# Relays.net
KiCad netlist of a schematic drawn in Altium Designer
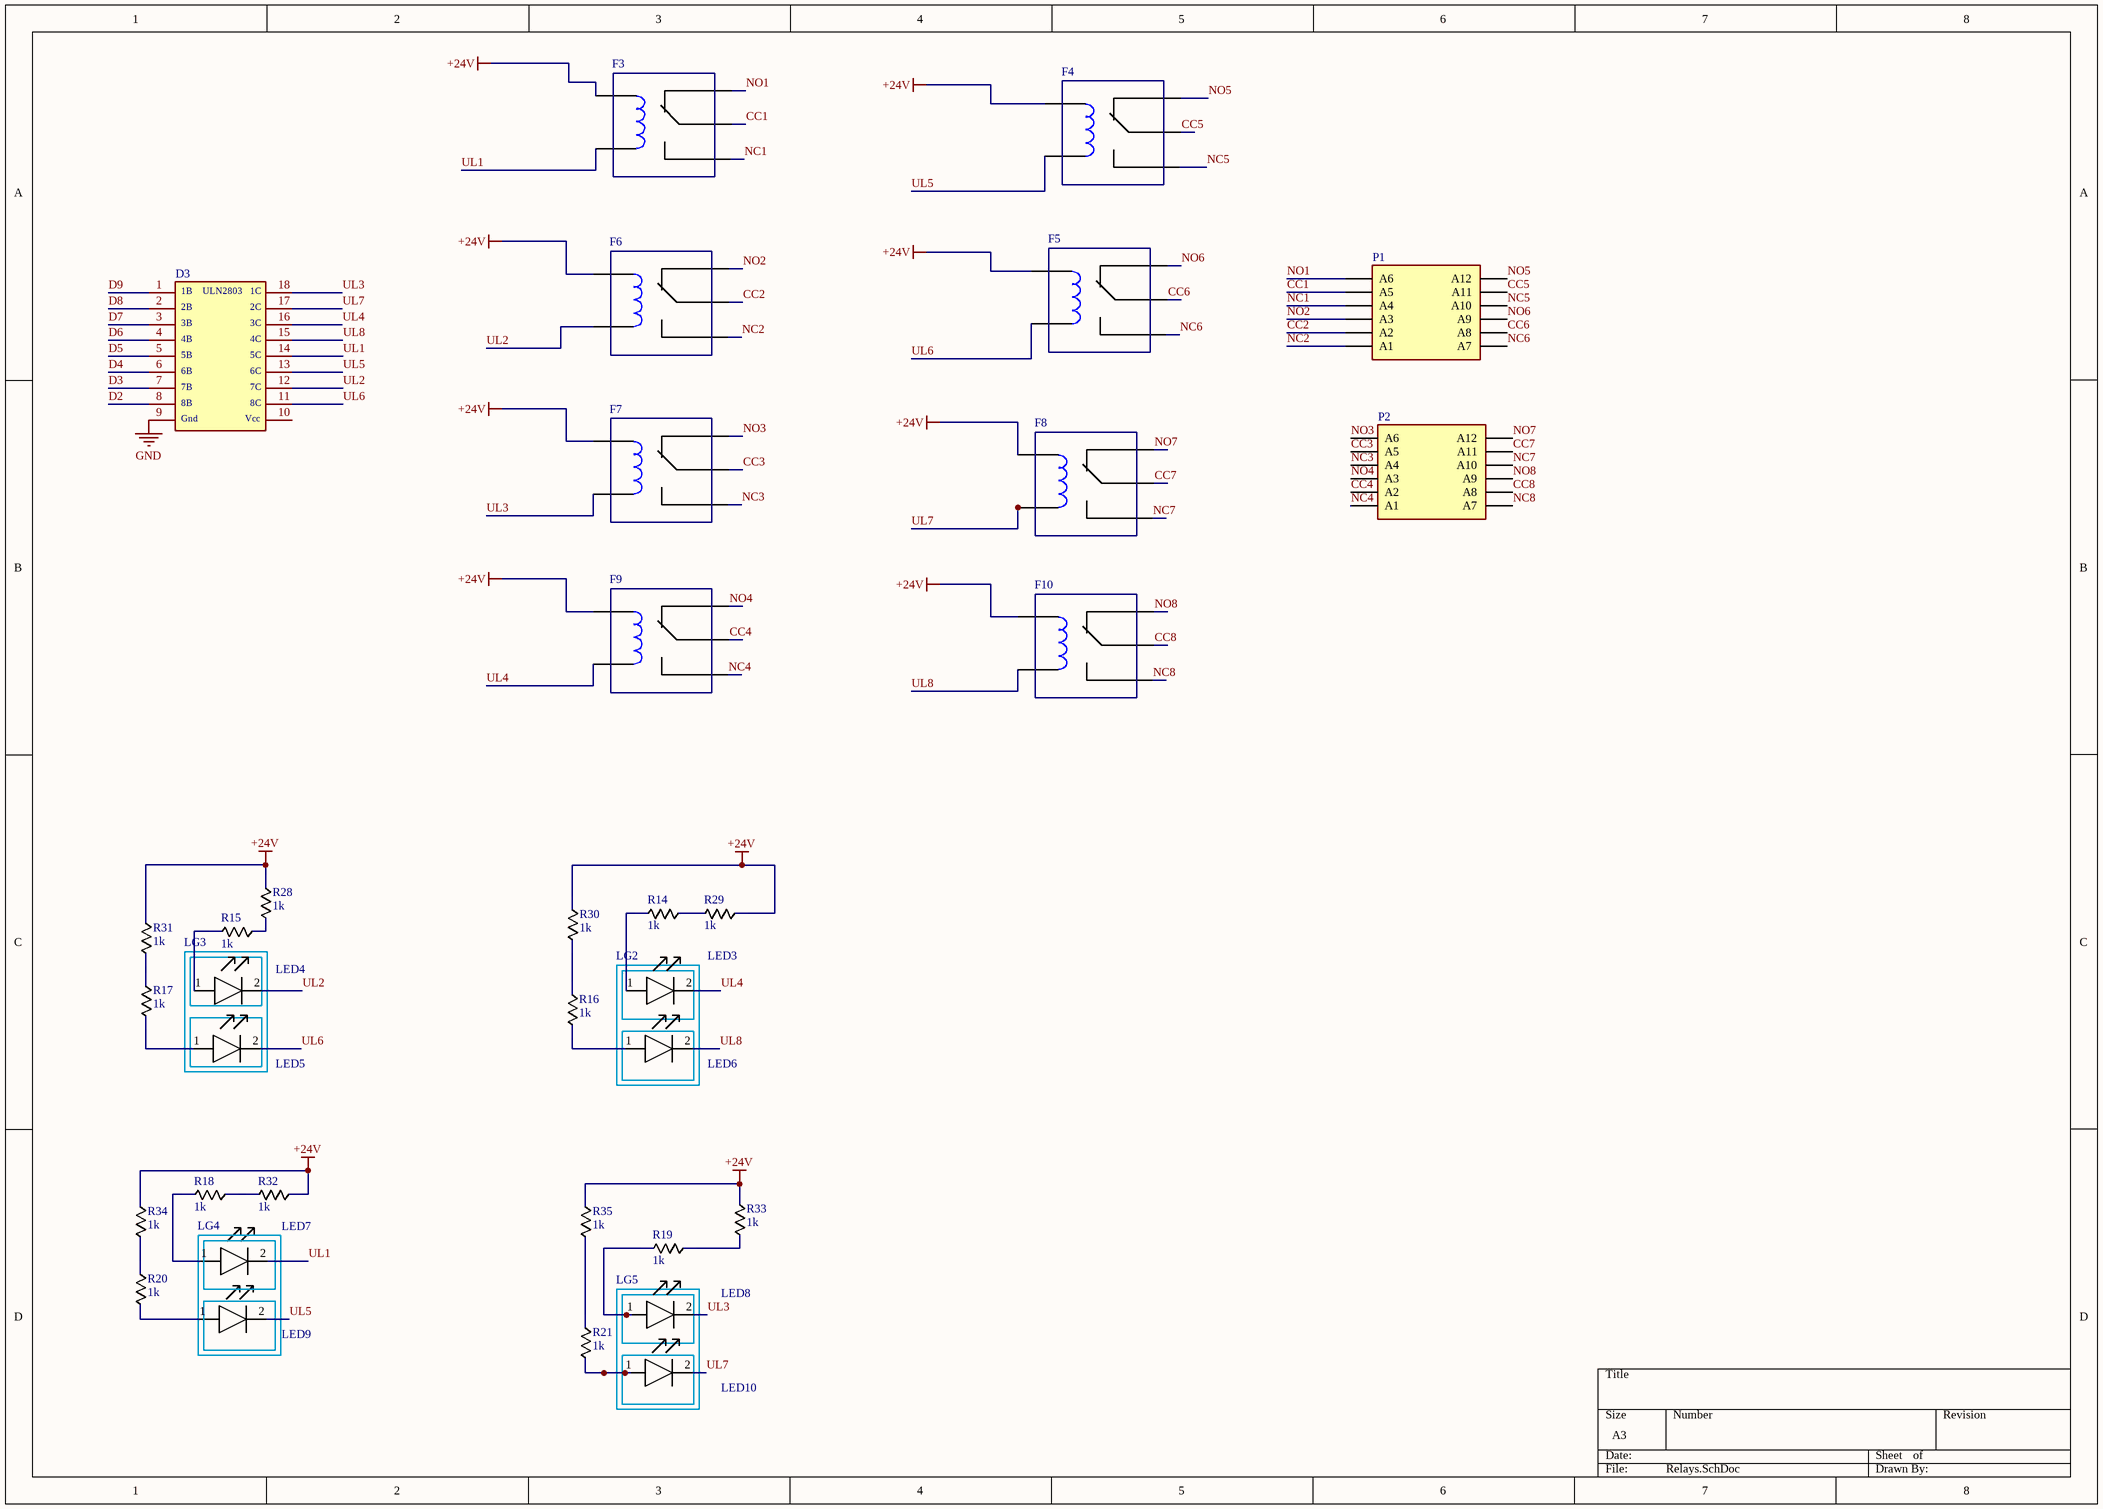
[diagram p0: Relays.SchDoc]

(export (version "E")
  (design (tool "Eeschema 10.0.6"))
  (components
    (comp (ref "D3")
      (value "~")
      (footprint "SOIC 18")
      (fields (field (name "PART NUMBER") "ULN2803ADWR"))
      (libsource (lib "kontr") (part "ULN2803 Darlington_1"))
    )
    (comp (ref "F3")
      (value "~")
      (footprint "413190240010")
      (fields (field (name "PART NUMBER") "G2RL124DC"))
      (libsource (lib "altium-import") (part "root_2__kontr.SCHLIB"))
    )
    (comp (ref "F4")
      (value "~")
      (footprint "413190240010")
      (fields (field (name "PART NUMBER") "G2RL124DC"))
      (libsource (lib "altium-import") (part "root_2__kontr.SCHLIB"))
    )
    (comp (ref "F5")
      (value "~")
      (footprint "413190240010")
      (fields (field (name "PART NUMBER") "G2RL124DC"))
      (libsource (lib "altium-import") (part "root_2__kontr.SCHLIB"))
    )
    (comp (ref "F6")
      (value "~")
      (footprint "413190240010")
      (fields (field (name "PART NUMBER") "G2RL124DC"))
      (libsource (lib "altium-import") (part "root_2__kontr.SCHLIB"))
    )
    (comp (ref "F7")
      (value "~")
      (footprint "413190240010")
      (fields (field (name "PART NUMBER") "G2RL124DC"))
      (libsource (lib "altium-import") (part "root_2__kontr.SCHLIB"))
    )
    (comp (ref "F8")
      (value "~")
      (footprint "413190240010")
      (fields (field (name "PART NUMBER") "G2RL124DC"))
      (libsource (lib "altium-import") (part "root_2__kontr.SCHLIB"))
    )
    (comp (ref "F9")
      (value "~")
      (footprint "413190240010")
      (fields (field (name "PART NUMBER") "G2RL124DC"))
      (libsource (lib "altium-import") (part "root_2__kontr.SCHLIB"))
    )
    (comp (ref "F10")
      (value "~")
      (footprint "413190240010")
      (fields (field (name "PART NUMBER") "G2RL124DC"))
      (libsource (lib "altium-import") (part "root_2__kontr.SCHLIB"))
    )
    (comp (ref "LED3")
      (value "~")
      (footprint "0603 - LED")
      (fields (field (name "PART NUMBER") "KP-1608SGC"))
      (libsource (lib "МЦТР.00010572.00.001") (part "LED 0603"))
    )
    (comp (ref "LED4")
      (value "~")
      (footprint "0603 - LED")
      (fields (field (name "PART NUMBER") "KP-1608SGC"))
      (libsource (lib "МЦТР.00010572.00.001") (part "LED 0603"))
    )
    (comp (ref "LED5")
      (value "~")
      (footprint "0603 - LED")
      (fields (field (name "PART NUMBER") "KP-1608SGC"))
      (libsource (lib "МЦТР.00010572.00.001") (part "LED 0603"))
    )
    (comp (ref "LED6")
      (value "~")
      (footprint "0603 - LED")
      (fields (field (name "PART NUMBER") "KP-1608SGC"))
      (libsource (lib "МЦТР.00010572.00.001") (part "LED 0603"))
    )
    (comp (ref "LED7")
      (value "~")
      (footprint "0603 - LED")
      (fields (field (name "PART NUMBER") "KP-1608SGC"))
      (libsource (lib "МЦТР.00010572.00.001") (part "LED 0603"))
    )
    (comp (ref "LED8")
      (value "~")
      (footprint "0603 - LED")
      (fields (field (name "PART NUMBER") "KP-1608SGC"))
      (libsource (lib "МЦТР.00010572.00.001") (part "LED 0603"))
    )
    (comp (ref "LED9")
      (value "~")
      (footprint "0603 - LED")
      (fields (field (name "PART NUMBER") "KP-1608SGC"))
      (libsource (lib "МЦТР.00010572.00.001") (part "LED 0603"))
    )
    (comp (ref "LED10")
      (value "~")
      (footprint "0603 - LED")
      (fields (field (name "PART NUMBER") "KP-1608SGC"))
      (libsource (lib "МЦТР.00010572.00.001") (part "LED 0603"))
    )
    (comp (ref "LG2")
      (value "~")
      (footprint "LED SMD DayLight")
      (fields (field (name "PART NUMBER") "5151094F"))
      (libsource (lib "МЦТР.00010572.00.001") (part "Light Guide 2"))
    )
    (comp (ref "LG3")
      (value "~")
      (footprint "LED SMD DayLight")
      (fields (field (name "PART NUMBER") "5151094F"))
      (libsource (lib "МЦТР.00010572.00.001") (part "Light Guide 2"))
    )
    (comp (ref "LG4")
      (value "~")
      (footprint "LED SMD DayLight")
      (fields (field (name "PART NUMBER") "5151094F"))
      (libsource (lib "МЦТР.00010572.00.001") (part "Light Guide 2"))
    )
    (comp (ref "LG5")
      (value "~")
      (footprint "LED SMD DayLight")
      (fields (field (name "PART NUMBER") "5151094F"))
      (libsource (lib "МЦТР.00010572.00.001") (part "Light Guide 2"))
    )
    (comp (ref "P1")
      (value "~")
      (footprint "LDO_lib:mcd 1,5/6-G1-3.81")
      (fields (field (name "PART NUMBER") "MCD 1.5/6 Phoenix") (field (name "PUBLISHER") "Altium Limited"))
      (libsource (lib "kontr") (part "MCD 1.5/6 Phoenix"))
    )
    (comp (ref "P2")
      (value "~")
      (footprint "LDO_lib:mcd 1,5/6-G1-3.81")
      (fields (field (name "PART NUMBER") "MCD 1.5/6 Phoenix") (field (name "PUBLISHER") "Altium Limited"))
      (libsource (lib "kontr") (part "MCD 1.5/6 Phoenix"))
    )
    (comp (ref "R14")
      (value "1k")
      (footprint "0603_Res")
      (fields (field (name "PART NUMBER") "RC0603FR-071KL"))
      (libsource (lib "kontr") (part "Resistor 0805"))
    )
    (comp (ref "R15")
      (value "1k")
      (footprint "0603_Res")
      (fields (field (name "PART NUMBER") "RC0603FR-071KL"))
      (libsource (lib "kontr") (part "Resistor 0805"))
    )
    (comp (ref "R16")
      (value "1k")
      (footprint "0603_Res")
      (fields (field (name "PART NUMBER") "RC0603FR-071KL"))
      (libsource (lib "kontr") (part "Resistor 0805"))
    )
    (comp (ref "R17")
      (value "1k")
      (footprint "0603_Res")
      (fields (field (name "PART NUMBER") "RC0603FR-071KL"))
      (libsource (lib "kontr") (part "Resistor 0805"))
    )
    (comp (ref "R18")
      (value "1k")
      (footprint "0603_Res")
      (fields (field (name "PART NUMBER") "RC0603FR-071KL"))
      (libsource (lib "kontr") (part "Resistor 0805"))
    )
    (comp (ref "R19")
      (value "1k")
      (footprint "0603_Res")
      (fields (field (name "PART NUMBER") "RC0603FR-071KL"))
      (libsource (lib "kontr") (part "Resistor 0805"))
    )
    (comp (ref "R20")
      (value "1k")
      (footprint "0603_Res")
      (fields (field (name "PART NUMBER") "RC0603FR-071KL"))
      (libsource (lib "kontr") (part "Resistor 0805"))
    )
    (comp (ref "R21")
      (value "1k")
      (footprint "0603_Res")
      (fields (field (name "PART NUMBER") "RC0603FR-071KL"))
      (libsource (lib "kontr") (part "Resistor 0805"))
    )
    (comp (ref "R28")
      (value "1k")
      (footprint "0603_Res")
      (fields (field (name "PART NUMBER") "RC0603FR-071KL"))
      (libsource (lib "kontr") (part "Resistor 0805"))
    )
    (comp (ref "R29")
      (value "1k")
      (footprint "0603_Res")
      (fields (field (name "PART NUMBER") "RC0603FR-071KL"))
      (libsource (lib "kontr") (part "Resistor 0805"))
    )
    (comp (ref "R30")
      (value "1k")
      (footprint "0603_Res")
      (fields (field (name "PART NUMBER") "RC0603FR-071KL"))
      (libsource (lib "kontr") (part "Resistor 0805"))
    )
    (comp (ref "R31")
      (value "1k")
      (footprint "0603_Res")
      (fields (field (name "PART NUMBER") "RC0603FR-071KL"))
      (libsource (lib "kontr") (part "Resistor 0805"))
    )
    (comp (ref "R32")
      (value "1k")
      (footprint "0603_Res")
      (fields (field (name "PART NUMBER") "RC0603FR-071KL"))
      (libsource (lib "kontr") (part "Resistor 0805"))
    )
    (comp (ref "R33")
      (value "1k")
      (footprint "0603_Res")
      (fields (field (name "PART NUMBER") "RC0603FR-071KL"))
      (libsource (lib "kontr") (part "Resistor 0805"))
    )
    (comp (ref "R34")
      (value "1k")
      (footprint "0603_Res")
      (fields (field (name "PART NUMBER") "RC0603FR-071KL"))
      (libsource (lib "kontr") (part "Resistor 0805"))
    )
    (comp (ref "R35")
      (value "1k")
      (footprint "0603_Res")
      (fields (field (name "PART NUMBER") "RC0603FR-071KL"))
      (libsource (lib "kontr") (part "Resistor 0805"))
    )
  )
  (nets
    (net (code "1") (name "+24V") (class "Default")
      (node (ref "F10") (pin "A2") (pinfunction "A2_A2") (pintype "passive"))
      (node (ref "F3") (pin "A2") (pinfunction "A2_A2") (pintype "passive"))
      (node (ref "F4") (pin "A2") (pinfunction "A2_A2") (pintype "passive"))
      (node (ref "F5") (pin "A2") (pinfunction "A2_A2") (pintype "passive"))
      (node (ref "F6") (pin "A2") (pinfunction "A2_A2") (pintype "passive"))
      (node (ref "F7") (pin "A2") (pinfunction "A2_A2") (pintype "passive"))
      (node (ref "F8") (pin "A2") (pinfunction "A2_A2") (pintype "passive"))
      (node (ref "F9") (pin "A2") (pinfunction "A2_A2") (pintype "passive"))
      (node (ref "R28") (pin "1") (pintype "passive"))
      (node (ref "R29") (pin "1") (pintype "passive"))
      (node (ref "R30") (pin "1") (pintype "passive"))
      (node (ref "R31") (pin "1") (pintype "passive"))
      (node (ref "R32") (pin "1") (pintype "passive"))
      (node (ref "R33") (pin "1") (pintype "passive"))
      (node (ref "R34") (pin "1") (pintype "passive"))
      (node (ref "R35") (pin "1") (pintype "passive"))
    )
    (net (code "2") (name "/CC1") (class "Default")
      (node (ref "F3") (pin "11") (pinfunction "11_11") (pintype "passive"))
      (node (ref "P1") (pin "3") (pinfunction "A5_3") (pintype "passive"))
    )
    (net (code "3") (name "/CC2") (class "Default")
      (node (ref "F6") (pin "11") (pinfunction "11_11") (pintype "passive"))
      (node (ref "P1") (pin "9") (pinfunction "A2_9") (pintype "passive"))
    )
    (net (code "4") (name "/CC3") (class "Default")
      (node (ref "F7") (pin "11") (pinfunction "11_11") (pintype "passive"))
      (node (ref "P2") (pin "3") (pinfunction "A5_3") (pintype "passive"))
    )
    (net (code "5") (name "/CC4") (class "Default")
      (node (ref "F9") (pin "11") (pinfunction "11_11") (pintype "passive"))
      (node (ref "P2") (pin "9") (pinfunction "A2_9") (pintype "passive"))
    )
    (net (code "6") (name "/CC5") (class "Default")
      (node (ref "F4") (pin "11") (pinfunction "11_11") (pintype "passive"))
      (node (ref "P1") (pin "4") (pinfunction "A11_4") (pintype "passive"))
    )
    (net (code "7") (name "/CC6") (class "Default")
      (node (ref "F5") (pin "11") (pinfunction "11_11") (pintype "passive"))
      (node (ref "P1") (pin "10") (pinfunction "A8_10") (pintype "passive"))
    )
    (net (code "8") (name "/CC7") (class "Default")
      (node (ref "F8") (pin "11") (pinfunction "11_11") (pintype "passive"))
      (node (ref "P2") (pin "4") (pinfunction "A11_4") (pintype "passive"))
    )
    (net (code "9") (name "/CC8") (class "Default")
      (node (ref "F10") (pin "11") (pinfunction "11_11") (pintype "passive"))
      (node (ref "P2") (pin "10") (pinfunction "A8_10") (pintype "passive"))
    )
    (net (code "10") (name "/D2") (class "Default")
      (node (ref "D3") (pin "8") (pinfunction "8_8") (pintype "passive"))
    )
    (net (code "11") (name "/D3") (class "Default")
      (node (ref "D3") (pin "7") (pinfunction "7_7") (pintype "passive"))
    )
    (net (code "12") (name "/D4") (class "Default")
      (node (ref "D3") (pin "6") (pinfunction "6_6") (pintype "passive"))
    )
    (net (code "13") (name "/D5") (class "Default")
      (node (ref "D3") (pin "5") (pinfunction "5_5") (pintype "passive"))
    )
    (net (code "14") (name "/D6") (class "Default")
      (node (ref "D3") (pin "4") (pinfunction "4_4") (pintype "passive"))
    )
    (net (code "15") (name "/D7") (class "Default")
      (node (ref "D3") (pin "3") (pinfunction "3_3") (pintype "passive"))
    )
    (net (code "16") (name "/D8") (class "Default")
      (node (ref "D3") (pin "2") (pinfunction "2_2") (pintype "passive"))
    )
    (net (code "17") (name "/D9") (class "Default")
      (node (ref "D3") (pin "1") (pinfunction "1_1") (pintype "passive"))
    )
    (net (code "18") (name "/NC1") (class "Default")
      (node (ref "F3") (pin "14") (pinfunction "1_14") (pintype "passive"))
      (node (ref "P1") (pin "5") (pinfunction "A4_5") (pintype "passive"))
    )
    (net (code "19") (name "/NC2") (class "Default")
      (node (ref "F6") (pin "14") (pinfunction "1_14") (pintype "passive"))
      (node (ref "P1") (pin "11") (pinfunction "A1_11") (pintype "passive"))
    )
    (net (code "20") (name "/NC3") (class "Default")
      (node (ref "F7") (pin "14") (pinfunction "1_14") (pintype "passive"))
      (node (ref "P2") (pin "5") (pinfunction "A4_5") (pintype "passive"))
    )
    (net (code "21") (name "/NC4") (class "Default")
      (node (ref "F9") (pin "14") (pinfunction "1_14") (pintype "passive"))
      (node (ref "P2") (pin "11") (pinfunction "A1_11") (pintype "passive"))
    )
    (net (code "22") (name "/NC5") (class "Default")
      (node (ref "F4") (pin "14") (pinfunction "1_14") (pintype "passive"))
      (node (ref "P1") (pin "6") (pinfunction "A10_6") (pintype "passive"))
    )
    (net (code "23") (name "/NC6") (class "Default")
      (node (ref "F5") (pin "14") (pinfunction "1_14") (pintype "passive"))
      (node (ref "P1") (pin "12") (pinfunction "A7_12") (pintype "passive"))
    )
    (net (code "24") (name "/NC7") (class "Default")
      (node (ref "F8") (pin "14") (pinfunction "1_14") (pintype "passive"))
      (node (ref "P2") (pin "6") (pinfunction "A10_6") (pintype "passive"))
    )
    (net (code "25") (name "/NC8") (class "Default")
      (node (ref "F10") (pin "14") (pinfunction "1_14") (pintype "passive"))
      (node (ref "P2") (pin "12") (pinfunction "A7_12") (pintype "passive"))
    )
    (net (code "26") (name "/NO1") (class "Default")
      (node (ref "F3") (pin "12") (pinfunction "12_12") (pintype "passive"))
      (node (ref "P1") (pin "1") (pinfunction "A6_1") (pintype "passive"))
    )
    (net (code "27") (name "/NO2") (class "Default")
      (node (ref "F6") (pin "12") (pinfunction "12_12") (pintype "passive"))
      (node (ref "P1") (pin "7") (pinfunction "A3_7") (pintype "passive"))
    )
    (net (code "28") (name "/NO3") (class "Default")
      (node (ref "F7") (pin "12") (pinfunction "12_12") (pintype "passive"))
      (node (ref "P2") (pin "1") (pinfunction "A6_1") (pintype "passive"))
    )
    (net (code "29") (name "/NO4") (class "Default")
      (node (ref "F9") (pin "12") (pinfunction "12_12") (pintype "passive"))
      (node (ref "P2") (pin "7") (pinfunction "A3_7") (pintype "passive"))
    )
    (net (code "30") (name "/NO5") (class "Default")
      (node (ref "F4") (pin "12") (pinfunction "12_12") (pintype "passive"))
      (node (ref "P1") (pin "2") (pinfunction "A12_2") (pintype "passive"))
    )
    (net (code "31") (name "/NO6") (class "Default")
      (node (ref "F5") (pin "12") (pinfunction "12_12") (pintype "passive"))
      (node (ref "P1") (pin "8") (pinfunction "A9_8") (pintype "passive"))
    )
    (net (code "32") (name "/NO7") (class "Default")
      (node (ref "F8") (pin "12") (pinfunction "12_12") (pintype "passive"))
      (node (ref "P2") (pin "2") (pinfunction "A12_2") (pintype "passive"))
    )
    (net (code "33") (name "/NO8") (class "Default")
      (node (ref "F10") (pin "12") (pinfunction "12_12") (pintype "passive"))
      (node (ref "P2") (pin "8") (pinfunction "A9_8") (pintype "passive"))
    )
    (net (code "34") (name "/UL1") (class "Default")
      (node (ref "D3") (pin "14") (pinfunction "14_14") (pintype "passive"))
      (node (ref "F3") (pin "A1") (pinfunction "A1_A1") (pintype "passive"))
      (node (ref "LED7") (pin "2") (pintype "passive"))
    )
    (net (code "35") (name "/UL2") (class "Default")
      (node (ref "D3") (pin "12") (pinfunction "12_12") (pintype "passive"))
      (node (ref "F6") (pin "A1") (pinfunction "A1_A1") (pintype "passive"))
      (node (ref "LED4") (pin "2") (pintype "passive"))
    )
    (net (code "36") (name "/UL3") (class "Default")
      (node (ref "D3") (pin "18") (pinfunction "18_18") (pintype "passive"))
      (node (ref "F7") (pin "A1") (pinfunction "A1_A1") (pintype "passive"))
      (node (ref "LED8") (pin "2") (pintype "passive"))
    )
    (net (code "37") (name "/UL4") (class "Default")
      (node (ref "D3") (pin "16") (pinfunction "16_16") (pintype "passive"))
      (node (ref "F9") (pin "A1") (pinfunction "A1_A1") (pintype "passive"))
      (node (ref "LED3") (pin "2") (pintype "passive"))
    )
    (net (code "38") (name "/UL5") (class "Default")
      (node (ref "D3") (pin "13") (pinfunction "13_13") (pintype "passive"))
      (node (ref "F4") (pin "A1") (pinfunction "A1_A1") (pintype "passive"))
      (node (ref "LED9") (pin "2") (pintype "passive"))
    )
    (net (code "39") (name "/UL6") (class "Default")
      (node (ref "D3") (pin "11") (pinfunction "11_11") (pintype "passive"))
      (node (ref "F5") (pin "A1") (pinfunction "A1_A1") (pintype "passive"))
      (node (ref "LED5") (pin "2") (pintype "passive"))
    )
    (net (code "40") (name "/UL7") (class "Default")
      (node (ref "D3") (pin "17") (pinfunction "17_17") (pintype "passive"))
      (node (ref "F8") (pin "A1") (pinfunction "A1_A1") (pintype "passive"))
      (node (ref "LED10") (pin "2") (pintype "passive"))
    )
    (net (code "41") (name "/UL8") (class "Default")
      (node (ref "D3") (pin "15") (pinfunction "15_15") (pintype "passive"))
      (node (ref "F10") (pin "A1") (pinfunction "A1_A1") (pintype "passive"))
      (node (ref "LED6") (pin "2") (pintype "passive"))
    )
    (net (code "42") (name "GND") (class "Default")
      (node (ref "D3") (pin "9") (pinfunction "9_9") (pintype "passive"))
    )
    (net (code "43") (name "Net-(LED3-Pad1)") (class "Default")
      (node (ref "LED3") (pin "1") (pintype "passive"))
      (node (ref "R14") (pin "2") (pintype "passive"))
    )
    (net (code "44") (name "Net-(LED4-Pad1)") (class "Default")
      (node (ref "LED4") (pin "1") (pintype "passive"))
      (node (ref "R15") (pin "2") (pintype "passive"))
    )
    (net (code "45") (name "Net-(LED5-Pad1)") (class "Default")
      (node (ref "LED5") (pin "1") (pintype "passive"))
      (node (ref "R17") (pin "2") (pintype "passive"))
    )
    (net (code "46") (name "Net-(LED6-Pad1)") (class "Default")
      (node (ref "LED6") (pin "1") (pintype "passive"))
      (node (ref "R16") (pin "2") (pintype "passive"))
    )
    (net (code "47") (name "Net-(LED7-Pad1)") (class "Default")
      (node (ref "LED7") (pin "1") (pintype "passive"))
      (node (ref "R18") (pin "2") (pintype "passive"))
    )
    (net (code "48") (name "Net-(LED8-Pad1)") (class "Default")
      (node (ref "LED8") (pin "1") (pintype "passive"))
      (node (ref "R19") (pin "2") (pintype "passive"))
    )
    (net (code "49") (name "Net-(LED9-Pad1)") (class "Default")
      (node (ref "LED9") (pin "1") (pintype "passive"))
      (node (ref "R20") (pin "2") (pintype "passive"))
    )
    (net (code "50") (name "Net-(LED10-Pad1)") (class "Default")
      (node (ref "LED10") (pin "1") (pintype "passive"))
      (node (ref "R21") (pin "2") (pintype "passive"))
    )
    (net (code "51") (name "Net-(R14-Pad1)") (class "Default")
      (node (ref "R14") (pin "1") (pintype "passive"))
      (node (ref "R29") (pin "2") (pintype "passive"))
    )
    (net (code "52") (name "Net-(R15-Pad1)") (class "Default")
      (node (ref "R15") (pin "1") (pintype "passive"))
      (node (ref "R28") (pin "2") (pintype "passive"))
    )
    (net (code "53") (name "Net-(R16-Pad1)") (class "Default")
      (node (ref "R16") (pin "1") (pintype "passive"))
      (node (ref "R30") (pin "2") (pintype "passive"))
    )
    (net (code "54") (name "Net-(R17-Pad1)") (class "Default")
      (node (ref "R17") (pin "1") (pintype "passive"))
      (node (ref "R31") (pin "2") (pintype "passive"))
    )
    (net (code "55") (name "Net-(R18-Pad1)") (class "Default")
      (node (ref "R18") (pin "1") (pintype "passive"))
      (node (ref "R32") (pin "2") (pintype "passive"))
    )
    (net (code "56") (name "Net-(R19-Pad1)") (class "Default")
      (node (ref "R19") (pin "1") (pintype "passive"))
      (node (ref "R33") (pin "2") (pintype "passive"))
    )
    (net (code "57") (name "Net-(R20-Pad1)") (class "Default")
      (node (ref "R20") (pin "1") (pintype "passive"))
      (node (ref "R34") (pin "2") (pintype "passive"))
    )
    (net (code "58") (name "Net-(R21-Pad1)") (class "Default")
      (node (ref "R21") (pin "1") (pintype "passive"))
      (node (ref "R35") (pin "2") (pintype "passive"))
    )
    (net (code "59") (name "unconnected-(D3-Pad10)") (class "Default")
      (node (ref "D3") (pin "10") (pinfunction "10_10") (pintype "passive"))
    )
  )
)
